# LED_DRIVER.net
KiCad netlist of a schematic drawn in Altium Designer
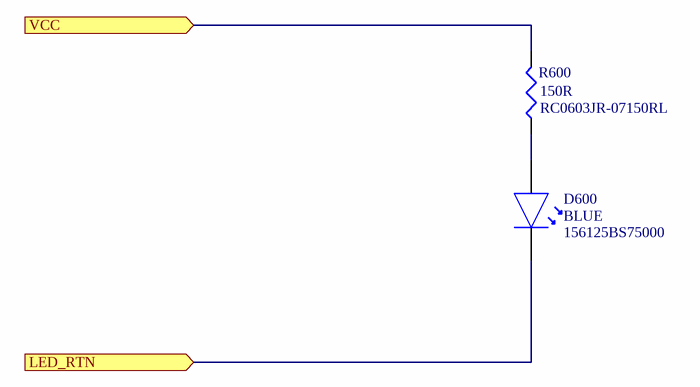
[diagram p0: LED DRIVER.SchDoc]

(export (version "E")
  (design (tool "Eeschema 10.0.6"))
  (components
    (comp (ref "D600")
      (value "BLUE")
      (footprint "WL-SMRW_1205_BLU")
      (description "WL-SMRW SMD MONO-COLOR REVERSE MOUNT. Blue 470nm LED Indication - Discrete 3.2V 1205 (3212 Metric)")
      (fields (field (name "MANUFACTURER PART NUMBER 1") "156125BS75000"))
      (libsource (lib "CubeSat-Backplane") (part "156125BS75000"))
    )
    (comp (ref "R600")
      (value "150R")
      (footprint "0603")
      (description "RES SMD 150 OHM 5% 1/10W 0603")
      (fields (field (name "MANUFACTURER PART NUMBER 1") "RC0603JR-07150RL") (field (name "TOLERANCE") "5%"))
      (libsource (lib "CubeSat-Backplane") (part "RES1"))
    )
  )
  (nets
    (net (code "1") (name "/LED_RTN") (class "Default")
      (node (ref "D600") (pin "K") (pinfunction "K_K") (pintype "passive"))
    )
    (net (code "2") (name "/VCC") (class "Default")
      (node (ref "R600") (pin "2") (pinfunction "2_2") (pintype "passive"))
    )
    (net (code "3") (name "Net-(D600-PadA)") (class "Default")
      (node (ref "D600") (pin "A") (pinfunction "A_A") (pintype "passive"))
      (node (ref "R600") (pin "1") (pinfunction "1_1") (pintype "passive"))
    )
  )
)
